# Debugger.net
KiCad netlist of a schematic drawn in Altium Designer
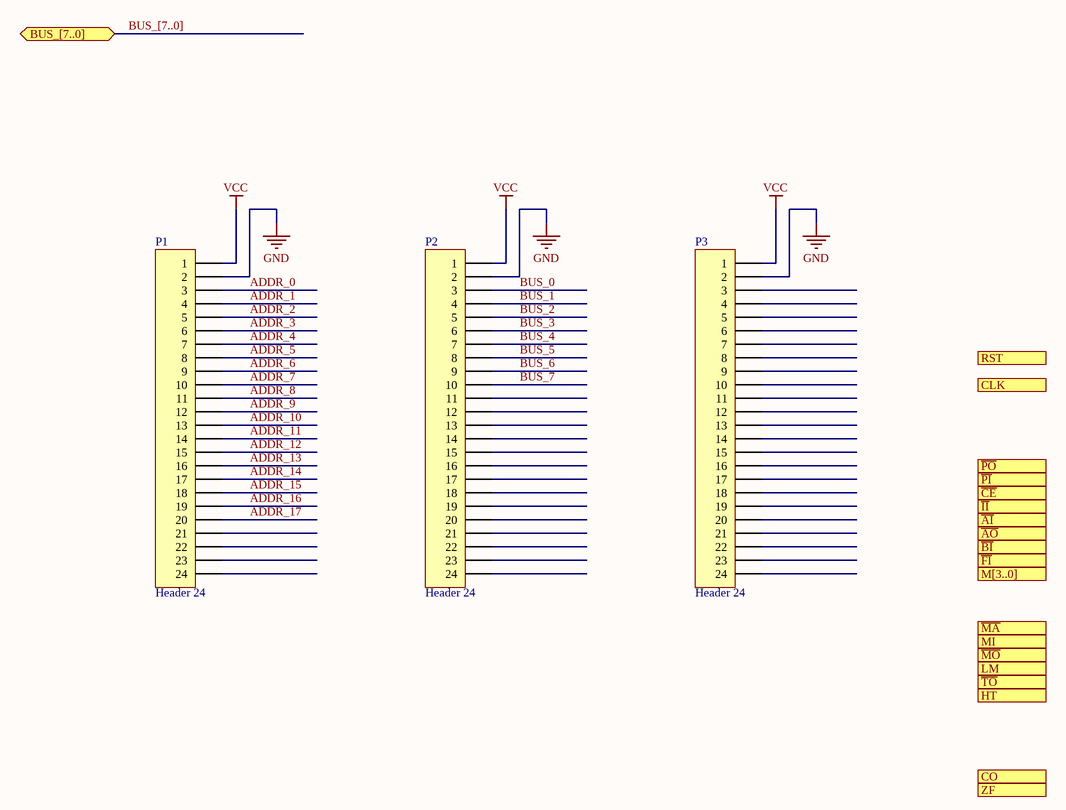
[diagram p0: Debugger.SchDoc]

(export (version "E")
  (design (tool "Eeschema 10.0.6"))
  (components
    (comp (ref "P1")
      (value "Header 24")
      (footprint "HDR1X24")
      (description "Header, 24-Pin")
      (fields (field (name "PUBLISHER") "Altium Limited"))
      (libsource (lib "Miscellaneous Connectors") (part "Header 24"))
    )
    (comp (ref "P2")
      (value "Header 24")
      (footprint "HDR1X24")
      (description "Header, 24-Pin")
      (fields (field (name "PUBLISHER") "Altium Limited"))
      (libsource (lib "Miscellaneous Connectors") (part "Header 24"))
    )
    (comp (ref "P3")
      (value "Header 24")
      (footprint "HDR1X24")
      (description "Header, 24-Pin")
      (fields (field (name "PUBLISHER") "Altium Limited"))
      (libsource (lib "Miscellaneous Connectors") (part "Header 24"))
    )
  )
  (nets
    (net (code "5") (name "/ADDR_0") (class "Default")
      (node (ref "P1") (pin "3") (pinfunction "3_3") (pintype "passive"))
    )
    (net (code "6") (name "/ADDR_1") (class "Default")
      (node (ref "P1") (pin "4") (pinfunction "4_4") (pintype "passive"))
    )
    (net (code "7") (name "/ADDR_2") (class "Default")
      (node (ref "P1") (pin "5") (pinfunction "5_5") (pintype "passive"))
    )
    (net (code "8") (name "/ADDR_3") (class "Default")
      (node (ref "P1") (pin "6") (pinfunction "6_6") (pintype "passive"))
    )
    (net (code "9") (name "/ADDR_4") (class "Default")
      (node (ref "P1") (pin "7") (pinfunction "7_7") (pintype "passive"))
    )
    (net (code "10") (name "/ADDR_5") (class "Default")
      (node (ref "P1") (pin "8") (pinfunction "8_8") (pintype "passive"))
    )
    (net (code "11") (name "/ADDR_6") (class "Default")
      (node (ref "P1") (pin "9") (pinfunction "9_9") (pintype "passive"))
    )
    (net (code "12") (name "/ADDR_7") (class "Default")
      (node (ref "P1") (pin "10") (pinfunction "10_10") (pintype "passive"))
    )
    (net (code "13") (name "/ADDR_8") (class "Default")
      (node (ref "P1") (pin "11") (pinfunction "11_11") (pintype "passive"))
    )
    (net (code "14") (name "/ADDR_9") (class "Default")
      (node (ref "P1") (pin "12") (pinfunction "12_12") (pintype "passive"))
    )
    (net (code "15") (name "/ADDR_10") (class "Default")
      (node (ref "P1") (pin "13") (pinfunction "13_13") (pintype "passive"))
    )
    (net (code "16") (name "/ADDR_11") (class "Default")
      (node (ref "P1") (pin "14") (pinfunction "14_14") (pintype "passive"))
    )
    (net (code "17") (name "/ADDR_12") (class "Default")
      (node (ref "P1") (pin "15") (pinfunction "15_15") (pintype "passive"))
    )
    (net (code "18") (name "/ADDR_13") (class "Default")
      (node (ref "P1") (pin "16") (pinfunction "16_16") (pintype "passive"))
    )
    (net (code "19") (name "/ADDR_14") (class "Default")
      (node (ref "P1") (pin "17") (pinfunction "17_17") (pintype "passive"))
    )
    (net (code "20") (name "/ADDR_15") (class "Default")
      (node (ref "P1") (pin "18") (pinfunction "18_18") (pintype "passive"))
    )
    (net (code "21") (name "/ADDR_16") (class "Default")
      (node (ref "P1") (pin "19") (pinfunction "19_19") (pintype "passive"))
    )
    (net (code "22") (name "/ADDR_17") (class "Default")
      (node (ref "P1") (pin "20") (pinfunction "20_20") (pintype "passive"))
    )
    (net (code "23") (name "/BUS_0") (class "Default")
      (node (ref "P2") (pin "3") (pinfunction "3_3") (pintype "passive"))
    )
    (net (code "24") (name "/BUS_1") (class "Default")
      (node (ref "P2") (pin "4") (pinfunction "4_4") (pintype "passive"))
    )
    (net (code "25") (name "/BUS_2") (class "Default")
      (node (ref "P2") (pin "5") (pinfunction "5_5") (pintype "passive"))
    )
    (net (code "26") (name "/BUS_3") (class "Default")
      (node (ref "P2") (pin "6") (pinfunction "6_6") (pintype "passive"))
    )
    (net (code "27") (name "/BUS_4") (class "Default")
      (node (ref "P2") (pin "7") (pinfunction "7_7") (pintype "passive"))
    )
    (net (code "28") (name "/BUS_5") (class "Default")
      (node (ref "P2") (pin "8") (pinfunction "8_8") (pintype "passive"))
    )
    (net (code "29") (name "/BUS_6") (class "Default")
      (node (ref "P2") (pin "9") (pinfunction "9_9") (pintype "passive"))
    )
    (net (code "30") (name "/BUS_7") (class "Default")
      (node (ref "P2") (pin "10") (pinfunction "10_10") (pintype "passive"))
    )
    (net (code "51") (name "GND") (class "Default")
      (node (ref "P1") (pin "2") (pinfunction "2_2") (pintype "passive"))
      (node (ref "P2") (pin "2") (pinfunction "2_2") (pintype "passive"))
      (node (ref "P3") (pin "2") (pinfunction "2_2") (pintype "passive"))
    )
    (net (code "52") (name "VCC") (class "Default")
      (node (ref "P1") (pin "1") (pinfunction "1_1") (pintype "passive"))
      (node (ref "P2") (pin "1") (pinfunction "1_1") (pintype "passive"))
      (node (ref "P3") (pin "1") (pinfunction "1_1") (pintype "passive"))
    )
    (net (code "53") (name "unconnected-(P1-Pad21)") (class "Default")
      (node (ref "P1") (pin "21") (pinfunction "21_21") (pintype "passive"))
    )
    (net (code "54") (name "unconnected-(P1-Pad22)") (class "Default")
      (node (ref "P1") (pin "22") (pinfunction "22_22") (pintype "passive"))
    )
    (net (code "55") (name "unconnected-(P1-Pad23)") (class "Default")
      (node (ref "P1") (pin "23") (pinfunction "23_23") (pintype "passive"))
    )
    (net (code "56") (name "unconnected-(P1-Pad24)") (class "Default")
      (node (ref "P1") (pin "24") (pinfunction "24_24") (pintype "passive"))
    )
    (net (code "57") (name "unconnected-(P2-Pad11)") (class "Default")
      (node (ref "P2") (pin "11") (pinfunction "11_11") (pintype "passive"))
    )
    (net (code "58") (name "unconnected-(P2-Pad12)") (class "Default")
      (node (ref "P2") (pin "12") (pinfunction "12_12") (pintype "passive"))
    )
    (net (code "59") (name "unconnected-(P2-Pad13)") (class "Default")
      (node (ref "P2") (pin "13") (pinfunction "13_13") (pintype "passive"))
    )
    (net (code "60") (name "unconnected-(P2-Pad14)") (class "Default")
      (node (ref "P2") (pin "14") (pinfunction "14_14") (pintype "passive"))
    )
    (net (code "61") (name "unconnected-(P2-Pad15)") (class "Default")
      (node (ref "P2") (pin "15") (pinfunction "15_15") (pintype "passive"))
    )
    (net (code "62") (name "unconnected-(P2-Pad16)") (class "Default")
      (node (ref "P2") (pin "16") (pinfunction "16_16") (pintype "passive"))
    )
    (net (code "63") (name "unconnected-(P2-Pad17)") (class "Default")
      (node (ref "P2") (pin "17") (pinfunction "17_17") (pintype "passive"))
    )
    (net (code "64") (name "unconnected-(P2-Pad18)") (class "Default")
      (node (ref "P2") (pin "18") (pinfunction "18_18") (pintype "passive"))
    )
    (net (code "65") (name "unconnected-(P2-Pad19)") (class "Default")
      (node (ref "P2") (pin "19") (pinfunction "19_19") (pintype "passive"))
    )
    (net (code "66") (name "unconnected-(P2-Pad20)") (class "Default")
      (node (ref "P2") (pin "20") (pinfunction "20_20") (pintype "passive"))
    )
    (net (code "67") (name "unconnected-(P2-Pad21)") (class "Default")
      (node (ref "P2") (pin "21") (pinfunction "21_21") (pintype "passive"))
    )
    (net (code "68") (name "unconnected-(P2-Pad22)") (class "Default")
      (node (ref "P2") (pin "22") (pinfunction "22_22") (pintype "passive"))
    )
    (net (code "69") (name "unconnected-(P2-Pad23)") (class "Default")
      (node (ref "P2") (pin "23") (pinfunction "23_23") (pintype "passive"))
    )
    (net (code "70") (name "unconnected-(P2-Pad24)") (class "Default")
      (node (ref "P2") (pin "24") (pinfunction "24_24") (pintype "passive"))
    )
    (net (code "71") (name "unconnected-(P3-Pad3)") (class "Default")
      (node (ref "P3") (pin "3") (pinfunction "3_3") (pintype "passive"))
    )
    (net (code "72") (name "unconnected-(P3-Pad4)") (class "Default")
      (node (ref "P3") (pin "4") (pinfunction "4_4") (pintype "passive"))
    )
    (net (code "73") (name "unconnected-(P3-Pad5)") (class "Default")
      (node (ref "P3") (pin "5") (pinfunction "5_5") (pintype "passive"))
    )
    (net (code "74") (name "unconnected-(P3-Pad6)") (class "Default")
      (node (ref "P3") (pin "6") (pinfunction "6_6") (pintype "passive"))
    )
    (net (code "75") (name "unconnected-(P3-Pad7)") (class "Default")
      (node (ref "P3") (pin "7") (pinfunction "7_7") (pintype "passive"))
    )
    (net (code "76") (name "unconnected-(P3-Pad8)") (class "Default")
      (node (ref "P3") (pin "8") (pinfunction "8_8") (pintype "passive"))
    )
    (net (code "77") (name "unconnected-(P3-Pad9)") (class "Default")
      (node (ref "P3") (pin "9") (pinfunction "9_9") (pintype "passive"))
    )
    (net (code "78") (name "unconnected-(P3-Pad10)") (class "Default")
      (node (ref "P3") (pin "10") (pinfunction "10_10") (pintype "passive"))
    )
    (net (code "79") (name "unconnected-(P3-Pad11)") (class "Default")
      (node (ref "P3") (pin "11") (pinfunction "11_11") (pintype "passive"))
    )
    (net (code "80") (name "unconnected-(P3-Pad12)") (class "Default")
      (node (ref "P3") (pin "12") (pinfunction "12_12") (pintype "passive"))
    )
    (net (code "81") (name "unconnected-(P3-Pad13)") (class "Default")
      (node (ref "P3") (pin "13") (pinfunction "13_13") (pintype "passive"))
    )
    (net (code "82") (name "unconnected-(P3-Pad14)") (class "Default")
      (node (ref "P3") (pin "14") (pinfunction "14_14") (pintype "passive"))
    )
    (net (code "83") (name "unconnected-(P3-Pad15)") (class "Default")
      (node (ref "P3") (pin "15") (pinfunction "15_15") (pintype "passive"))
    )
    (net (code "84") (name "unconnected-(P3-Pad16)") (class "Default")
      (node (ref "P3") (pin "16") (pinfunction "16_16") (pintype "passive"))
    )
    (net (code "85") (name "unconnected-(P3-Pad17)") (class "Default")
      (node (ref "P3") (pin "17") (pinfunction "17_17") (pintype "passive"))
    )
    (net (code "86") (name "unconnected-(P3-Pad18)") (class "Default")
      (node (ref "P3") (pin "18") (pinfunction "18_18") (pintype "passive"))
    )
    (net (code "87") (name "unconnected-(P3-Pad19)") (class "Default")
      (node (ref "P3") (pin "19") (pinfunction "19_19") (pintype "passive"))
    )
    (net (code "88") (name "unconnected-(P3-Pad20)") (class "Default")
      (node (ref "P3") (pin "20") (pinfunction "20_20") (pintype "passive"))
    )
    (net (code "89") (name "unconnected-(P3-Pad21)") (class "Default")
      (node (ref "P3") (pin "21") (pinfunction "21_21") (pintype "passive"))
    )
    (net (code "90") (name "unconnected-(P3-Pad22)") (class "Default")
      (node (ref "P3") (pin "22") (pinfunction "22_22") (pintype "passive"))
    )
    (net (code "91") (name "unconnected-(P3-Pad23)") (class "Default")
      (node (ref "P3") (pin "23") (pinfunction "23_23") (pintype "passive"))
    )
    (net (code "92") (name "unconnected-(P3-Pad24)") (class "Default")
      (node (ref "P3") (pin "24") (pinfunction "24_24") (pintype "passive"))
    )
  )
)
